# ohms-law.net
KiCad netlist of a schematic drawn in EAGLE
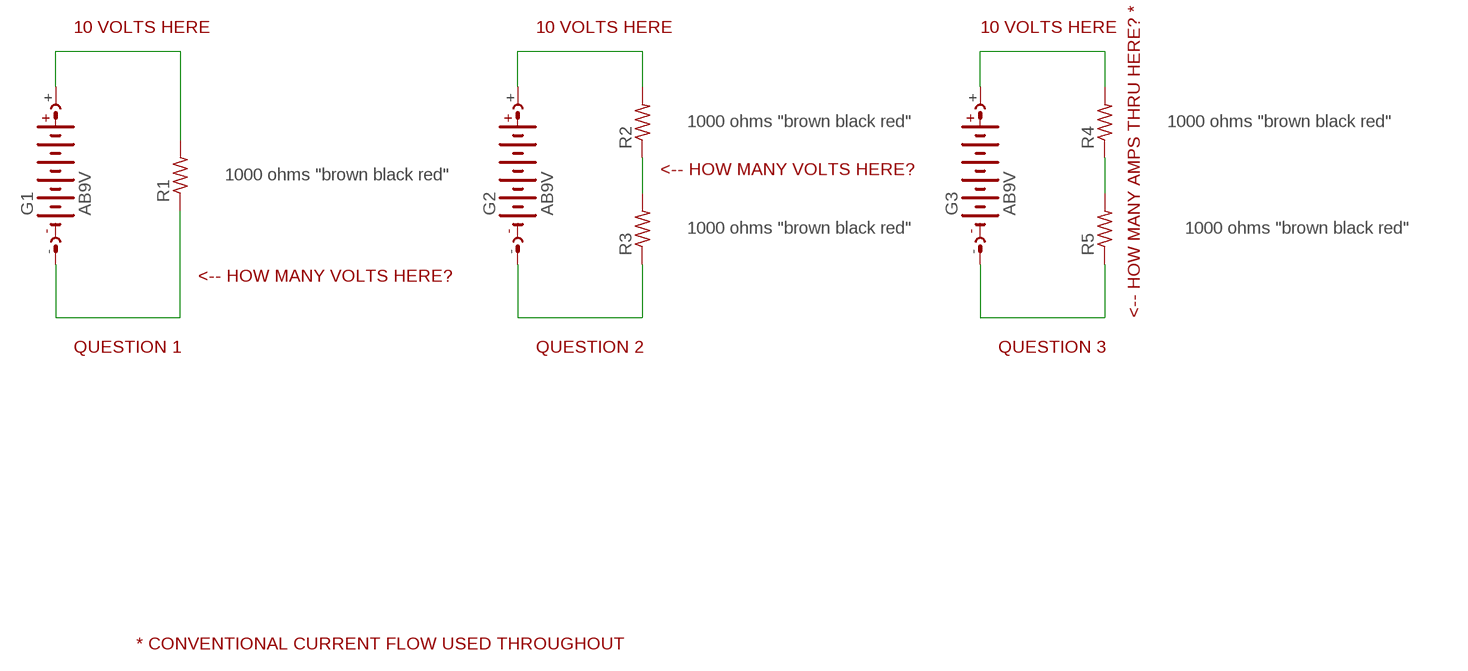
[diagram p0: schematic, sheet 1]

(export (version "E")
  (design (tool "Eeschema 10.0.6"))
  (components
    (comp (ref "G1")
      (value "AB9V")
      (footprint "eagle-import:AB9V")
      (libsource (lib "eagle-import") (part "AB9V"))
    )
    (comp (ref "G2")
      (value "AB9V")
      (footprint "eagle-import:AB9V")
      (libsource (lib "eagle-import") (part "AB9V"))
    )
    (comp (ref "G3")
      (value "AB9V")
      (footprint "eagle-import:AB9V")
      (libsource (lib "eagle-import") (part "AB9V"))
    )
    (comp (ref "R1")
      (value "1000 ohms \"brown black red\"")
      (footprint "eagle-import:M0805")
      (libsource (lib "eagle-import") (part "R-US_M0805"))
    )
    (comp (ref "R2")
      (value "1000 ohms \"brown black red\"")
      (footprint "eagle-import:M0805")
      (libsource (lib "eagle-import") (part "R-US_M0805"))
    )
    (comp (ref "R3")
      (value "1000 ohms \"brown black red\"")
      (footprint "eagle-import:M0805")
      (libsource (lib "eagle-import") (part "R-US_M0805"))
    )
    (comp (ref "R4")
      (value "1000 ohms \"brown black red\"")
      (footprint "eagle-import:M0805")
      (libsource (lib "eagle-import") (part "R-US_M0805"))
    )
    (comp (ref "R5")
      (value "1000 ohms \"brown black red\"")
      (footprint "eagle-import:M0805")
      (libsource (lib "eagle-import") (part "R-US_M0805"))
    )
  )
  (nets
    (net (code "1") (name "Net-(G1-Pad+)") (class "Default")
      (node (ref "G1") (pin "+") (pinfunction "+_+") (pintype "passive"))
      (node (ref "R1") (pin "2") (pinfunction "2_2") (pintype "passive"))
    )
    (net (code "2") (name "Net-(G1-Pad-)") (class "Default")
      (node (ref "G1") (pin "-") (pinfunction "-_-") (pintype "passive"))
      (node (ref "R1") (pin "1") (pinfunction "1_1") (pintype "passive"))
    )
    (net (code "3") (name "Net-(G2-Pad+)") (class "Default")
      (node (ref "G2") (pin "+") (pinfunction "+_+") (pintype "passive"))
      (node (ref "R2") (pin "2") (pinfunction "2_2") (pintype "passive"))
    )
    (net (code "4") (name "Net-(G2-Pad-)") (class "Default")
      (node (ref "G2") (pin "-") (pinfunction "-_-") (pintype "passive"))
      (node (ref "R3") (pin "1") (pinfunction "1_1") (pintype "passive"))
    )
    (net (code "5") (name "Net-(G3-Pad+)") (class "Default")
      (node (ref "G3") (pin "+") (pinfunction "+_+") (pintype "passive"))
      (node (ref "R4") (pin "2") (pinfunction "2_2") (pintype "passive"))
    )
    (net (code "6") (name "Net-(G3-Pad-)") (class "Default")
      (node (ref "G3") (pin "-") (pinfunction "-_-") (pintype "passive"))
      (node (ref "R5") (pin "1") (pinfunction "1_1") (pintype "passive"))
    )
    (net (code "7") (name "Net-(R2-Pad1)") (class "Default")
      (node (ref "R2") (pin "1") (pinfunction "1_1") (pintype "passive"))
      (node (ref "R3") (pin "2") (pinfunction "2_2") (pintype "passive"))
    )
    (net (code "8") (name "Net-(R4-Pad1)") (class "Default")
      (node (ref "R4") (pin "1") (pinfunction "1_1") (pintype "passive"))
      (node (ref "R5") (pin "2") (pinfunction "2_2") (pintype "passive"))
    )
  )
)
